# TB_sch.net
KiCad netlist of a schematic drawn in Altium Designer
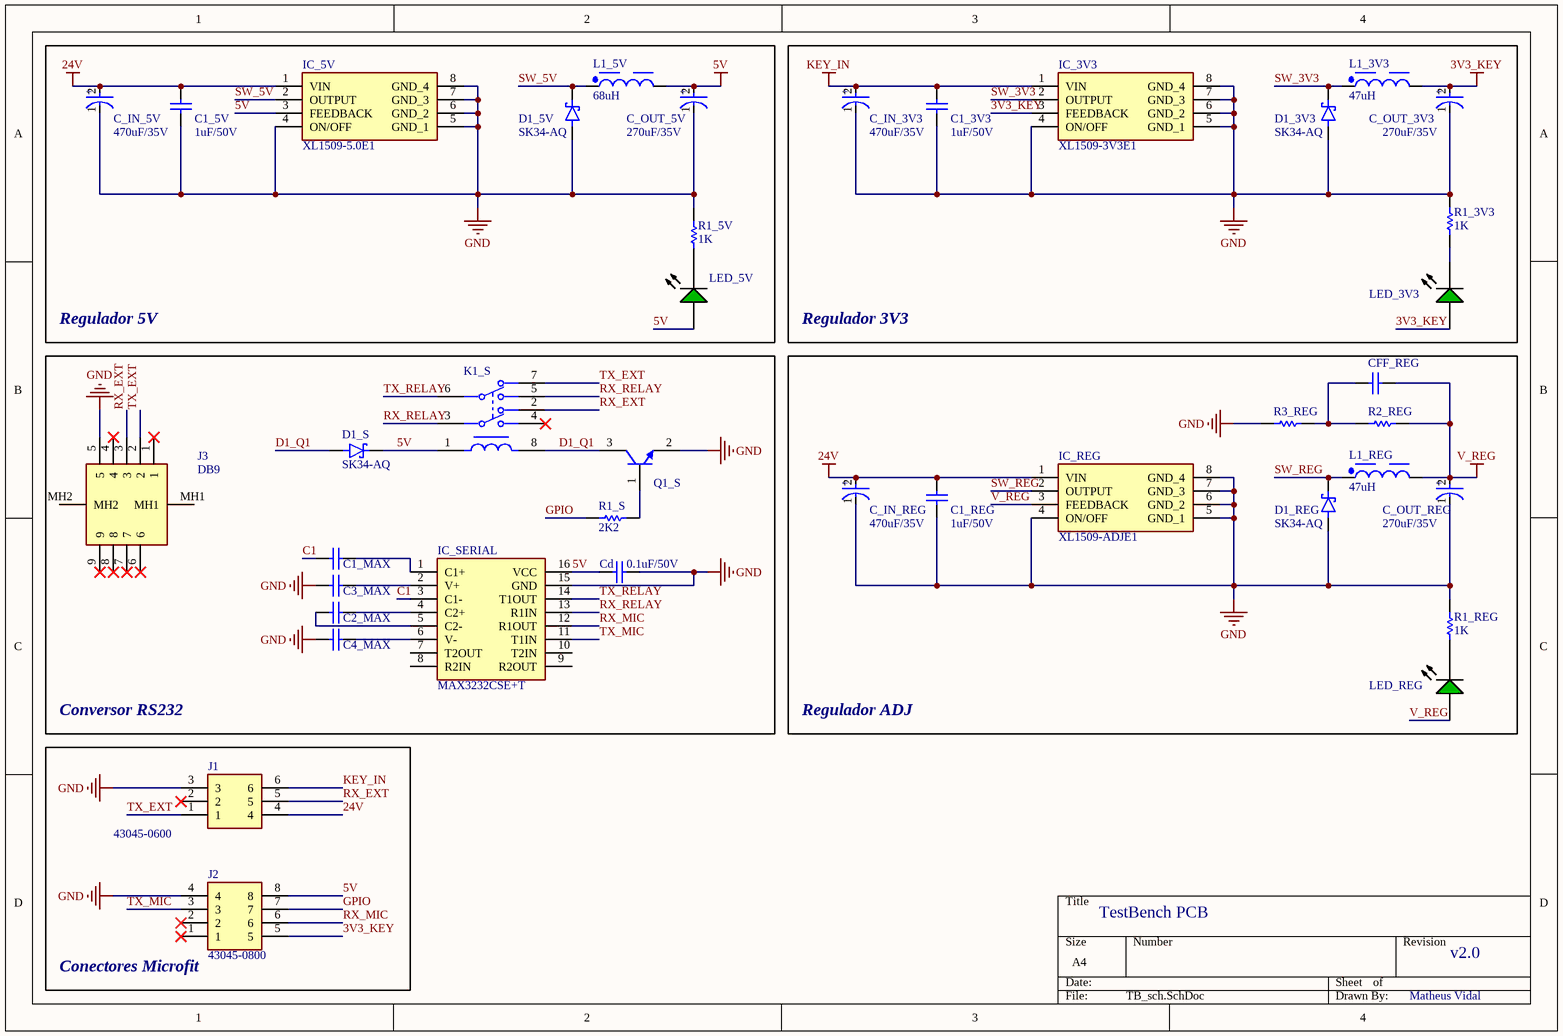
[diagram p0: TB_sch.SchDoc]

(export (version "E")
  (design (tool "Eeschema 10.0.6"))
  (components
    (comp (ref "C1_3V3")
      (value "1uF/50V")
      (footprint "CAPC2013X135X45LL10T25")
      (description "Chip Capacitor, 4.7 uF, +/- 10%, 16 V, -55 to 85 degC, 0805 (2012 Metric), RoHS, Tape and Reel")
      (fields (field (name "TOLERANCE") "10%") (field (name "PARTNUMBER") "GRM21BR61C475KA88L"))
      (libsource (lib "Altium Content Vault") (part "CAP-NP-2"))
    )
    (comp (ref "C1_5V")
      (value "1uF/50V")
      (footprint "CAPC2013X135X45LL10T25")
      (description "Chip Capacitor, 4.7 uF, +/- 10%, 16 V, -55 to 85 degC, 0805 (2012 Metric), RoHS, Tape and Reel")
      (fields (field (name "TOLERANCE") "10%") (field (name "PARTNUMBER") "GRM21BR61C475KA88L"))
      (libsource (lib "Altium Content Vault") (part "CAP-NP-2"))
    )
    (comp (ref "C1_MAX")
      (value "0.1uF/50V")
      (footprint "CAPC2013X135X45LL10T25")
      (description "Chip Capacitor, 4.7 uF, +/- 10%, 16 V, -55 to 85 degC, 0805 (2012 Metric), RoHS, Tape and Reel")
      (fields (field (name "TOLERANCE") "10%") (field (name "PARTNUMBER") "GRM21BR61C475KA88L"))
      (libsource (lib "Altium Content Vault") (part "CAP-NP-2"))
    )
    (comp (ref "C1_REG")
      (value "1uF/50V")
      (footprint "CAPC2013X135X45LL10T25")
      (description "Chip Capacitor, 4.7 uF, +/- 10%, 16 V, -55 to 85 degC, 0805 (2012 Metric), RoHS, Tape and Reel")
      (fields (field (name "TOLERANCE") "10%") (field (name "PARTNUMBER") "GRM21BR61C475KA88L"))
      (libsource (lib "Altium Content Vault") (part "CAP-NP-2"))
    )
    (comp (ref "C2_MAX")
      (value "0.1uF/50V")
      (footprint "CAPC2013X135X45LL10T25")
      (description "Chip Capacitor, 4.7 uF, +/- 10%, 16 V, -55 to 85 degC, 0805 (2012 Metric), RoHS, Tape and Reel")
      (fields (field (name "TOLERANCE") "10%") (field (name "PARTNUMBER") "GRM21BR61C475KA88L"))
      (libsource (lib "Altium Content Vault") (part "CAP-NP-2"))
    )
    (comp (ref "C3_MAX")
      (value "0.1uF/50V")
      (footprint "CAPC2013X135X45LL10T25")
      (description "Chip Capacitor, 4.7 uF, +/- 10%, 16 V, -55 to 85 degC, 0805 (2012 Metric), RoHS, Tape and Reel")
      (fields (field (name "TOLERANCE") "10%") (field (name "PARTNUMBER") "GRM21BR61C475KA88L"))
      (libsource (lib "Altium Content Vault") (part "CAP-NP-2"))
    )
    (comp (ref "C4_MAX")
      (value "0.1uF/50V")
      (footprint "CAPC2013X135X45LL10T25")
      (description "Chip Capacitor, 4.7 uF, +/- 10%, 16 V, -55 to 85 degC, 0805 (2012 Metric), RoHS, Tape and Reel")
      (fields (field (name "TOLERANCE") "10%") (field (name "PARTNUMBER") "GRM21BR61C475KA88L"))
      (libsource (lib "Altium Content Vault") (part "CAP-NP-2"))
    )
    (comp (ref "Cd")
      (value "0.1uF/50V")
      (footprint "CAPC2013X135X45LL10T25")
      (description "Chip Capacitor, 4.7 uF, +/- 10%, 16 V, -55 to 85 degC, 0805 (2012 Metric), RoHS, Tape and Reel")
      (fields (field (name "TOLERANCE") "10%") (field (name "PARTNUMBER") "GRM21BR61C475KA88L"))
      (libsource (lib "Altium Content Vault") (part "CAP-NP-2"))
    )
    (comp (ref "CFF_REG")
      (value "3.3nF/50V")
      (footprint "CAPC2013X135X45LL10T25")
      (description "Chip Capacitor, 4.7 uF, +/- 10%, 16 V, -55 to 85 degC, 0805 (2012 Metric), RoHS, Tape and Reel")
      (fields (field (name "TOLERANCE") "10%") (field (name "PARTNUMBER") "GRM21BR61C475KA88L"))
      (libsource (lib "Altium Content Vault") (part "CAP-NP-2"))
    )
    (comp (ref "C_IN_3V3")
      (value "470uF/35V")
      (footprint "FP-UCW1H221MNL1GS-MFG")
      (description "CAP ALUM 220UF 20% 50V SMD")
      (fields (field (name "TOLERANCE") "20%") (field (name "VOLTAGE") "50V"))
      (libsource (lib "Altium Content Vault") (part "cf48714ba7e38822c1575c7ec0b6d1f"))
    )
    (comp (ref "C_IN_5V")
      (value "470uF/35V")
      (footprint "FP-UCW1H221MNL1GS-MFG")
      (description "CAP ALUM 220UF 20% 50V SMD")
      (fields (field (name "TOLERANCE") "20%") (field (name "VOLTAGE") "50V"))
      (libsource (lib "Altium Content Vault") (part "cf48714ba7e38822c1575c7ec0b6d1f"))
    )
    (comp (ref "C_IN_REG")
      (value "470uF/35V")
      (footprint "FP-UCW1H221MNL1GS-MFG")
      (description "CAP ALUM 220UF 20% 50V SMD")
      (fields (field (name "TOLERANCE") "20%") (field (name "VOLTAGE") "50V"))
      (libsource (lib "Altium Content Vault") (part "cf48714ba7e38822c1575c7ec0b6d1f"))
    )
    (comp (ref "C_OUT_3V3")
      (value "270uF/35V")
      (footprint "FP-UCW1H221MNL1GS-MFG")
      (description "CAP ALUM 220UF 20% 50V SMD")
      (fields (field (name "TOLERANCE") "20%") (field (name "VOLTAGE") "50V"))
      (libsource (lib "Altium Content Vault") (part "cf48714ba7e38822c1575c7ec0b6d1f"))
    )
    (comp (ref "C_OUT_5V")
      (value "270uF/35V")
      (footprint "FP-UCW1H221MNL1GS-MFG")
      (description "CAP ALUM 220UF 20% 50V SMD")
      (fields (field (name "TOLERANCE") "20%") (field (name "VOLTAGE") "50V"))
      (libsource (lib "Altium Content Vault") (part "cf48714ba7e38822c1575c7ec0b6d1f"))
    )
    (comp (ref "C_OUT_REG")
      (value "270uF/35V")
      (footprint "FP-UCW1H221MNL1GS-MFG")
      (description "CAP ALUM 220UF 20% 50V SMD")
      (fields (field (name "TOLERANCE") "20%") (field (name "VOLTAGE") "50V"))
      (libsource (lib "Altium Content Vault") (part "cf48714ba7e38822c1575c7ec0b6d1f"))
    )
    (comp (ref "D1_3V3")
      (value "SK34-AQ")
      (footprint "DIOM7958X250N")
      (fields (field (name "MF") "Diotec Semiconductor"))
      (libsource (lib "SK34-AQ") (part "SK34-AQ"))
    )
    (comp (ref "D1_5V")
      (value "SK34-AQ")
      (footprint "DIOM7958X250N")
      (fields (field (name "MF") "Diotec Semiconductor"))
      (libsource (lib "SK34-AQ") (part "SK34-AQ"))
    )
    (comp (ref "D1_REG")
      (value "SK34-AQ")
      (footprint "DIOM7958X250N")
      (fields (field (name "MF") "Diotec Semiconductor"))
      (libsource (lib "SK34-AQ") (part "SK34-AQ"))
    )
    (comp (ref "D1_S")
      (value "SK34-AQ")
      (footprint "DIOM7958X250N")
      (fields (field (name "MF") "Diotec Semiconductor"))
      (libsource (lib "SK34-AQ") (part "SK34-AQ"))
    )
    (comp (ref "IC_3V3")
      (value "XL1509-3V3E1")
      (footprint "SamacSys:SOIC127P600X175-8N")
      (description "Integrated Circuit")
      (fields (field (name "MANUFACTURER_PART_NUMBER") "XL1509-5.0E1"))
      (libsource (lib "*") (part "XL1509-5.0E1"))
    )
    (comp (ref "IC_5V")
      (value "XL1509-5.0E1")
      (footprint "SamacSys:SOIC127P600X175-8N")
      (description "Integrated Circuit")
      (libsource (lib "*") (part "XL1509-5.0E1"))
    )
    (comp (ref "IC_REG")
      (value "XL1509-ADJE1")
      (footprint "SamacSys:SOIC127P600X175-8N")
      (description "Integrated Circuit")
      (fields (field (name "MANUFACTURER_PART_NUMBER") "XL1509-5.0E1"))
      (libsource (lib "*") (part "XL1509-5.0E1"))
    )
    (comp (ref "IC_SERIAL")
      (value "MAX3232CSE+T")
      (footprint "SamacSys:SOIC127P600X175-16N")
      (description "Integrated Circuit")
      (fields (field (name "MOUSER PART NUMBER") "700-MAX3232CSET"))
      (libsource (lib "*") (part "MAX3232CSE+T"))
    )
    (comp (ref "J1")
      (value "43045-0600")
      (footprint "SamacSys:43045-06(00,01,02,10)")
      (description "Connector")
      (fields (field (name "MOUSER PART NUMBER") "538-43045-0600"))
      (libsource (lib "*") (part "43045-0600"))
    )
    (comp (ref "J2")
      (value "43045-0800")
      (footprint "SamacSys:43045-08(00,01,02,10)")
      (description "Connector")
      (fields (field (name "MOUSER PART NUMBER") "538-43045-0800"))
      (libsource (lib "*") (part "43045-0800"))
    )
    (comp (ref "J3")
      (value "DB9")
      (footprint "SamacSys:L77DFE09S1AMN")
      (description "Connector")
      (fields
        (field (name "MANUFACTURER_PART_NUMBER") "L77DFE09S1AMN")
        (field (name "MOUSER PART NUMBER") "523-L77DFE09S1AMN")
      )
      (libsource (lib "*") (part "L77DFE09S1AMN"))
    )
    (comp (ref "K1_S")
      (value "G6K-2F-Y-TR-DC5")
      (footprint "FP-G6K-2F-Y-TR-DC5-MFG")
      (description "RELAY TELECOM DPDT 1A 5VDC")
      (fields
        (field (name "OCTOPART") "https://octopart.com/g6k-2f-y-tr-dc5-omron-697853")
        (field (name "MANUFACTURER") "Omron")
      )
      (libsource (lib "Altium Content Vault") (part "58c38101009d5ebbf9054263c5b66d6"))
    )
    (comp (ref "L1_3V3")
      (value "47uH")
      (footprint "WE-PD_1280")
      (fields (field (name "TOLERANCE") "20%"))
      (libsource (lib "Altium Content Vault") (part "Inductor - 2"))
    )
    (comp (ref "L1_5V")
      (value "68uH")
      (footprint "WE-PD_1280")
      (fields (field (name "TOLERANCE") "20%"))
      (libsource (lib "Altium Content Vault") (part "Inductor - 2"))
    )
    (comp (ref "L1_REG")
      (value "47uH")
      (footprint "WE-PD_1280")
      (fields (field (name "TOLERANCE") "20%"))
      (libsource (lib "Altium Content Vault") (part "Inductor - 2"))
    )
    (comp (ref "LED_3V3")
      (value "~")
      (footprint "AVAG-HSMX-C170_V")
      (description "Chip LED, Green, 2.2 V, -40 to 85 degC, 2-Pin SMD, Pb-Free, Tape and Reel")
      (fields (field (name "MANUFACTURER") "Avago"))
      (libsource (lib "Altium Content Vault") (part "LED_GREEN_A1K2-2"))
    )
    (comp (ref "LED_5V")
      (value "~")
      (footprint "AVAG-HSMX-C170_V")
      (description "Chip LED, Green, 2.2 V, -40 to 85 degC, 2-Pin SMD, Pb-Free, Tape and Reel")
      (fields (field (name "MANUFACTURER") "Avago"))
      (libsource (lib "Altium Content Vault") (part "LED_GREEN_A1K2-2"))
    )
    (comp (ref "LED_REG")
      (value "~")
      (footprint "AVAG-HSMX-C170_V")
      (description "Chip LED, Green, 2.2 V, -40 to 85 degC, 2-Pin SMD, Pb-Free, Tape and Reel")
      (fields (field (name "MANUFACTURER") "Avago"))
      (libsource (lib "Altium Content Vault") (part "LED_GREEN_A1K2-2"))
    )
    (comp (ref "Q1_S")
      (value "MMBT2222LT1G")
      (footprint "ONSC-SOT-23-3-318-08_V")
      (description "General Purpose Transistor, NPN Silicon, 3-Pin SOT-23, Pb-Free, Tape and Reel")
      (fields (field (name "MANUFACTURER") "On Semiconductor"))
      (libsource (lib "Altium Content Vault") (part "ONSC-NPN-B1E2C3-3"))
    )
    (comp (ref "R1_3V3")
      (value "1K")
      (footprint "RESC2013X50X30LL20T20")
      (fields (field (name "MANUFACTURER") "Vishay Dale") (field (name "PART NUMBER") "CRCW08050000Z0EA"))
      (libsource (lib "Altium Content Vault") (part "RES"))
    )
    (comp (ref "R1_5V")
      (value "1K")
      (footprint "RESC2013X50X30LL20T20")
      (fields (field (name "MANUFACTURER") "Vishay Dale") (field (name "PART NUMBER") "CRCW08050000Z0EA"))
      (libsource (lib "Altium Content Vault") (part "RES"))
    )
    (comp (ref "R1_REG")
      (value "1K")
      (footprint "RESC2013X50X30LL20T20")
      (fields (field (name "MANUFACTURER") "Vishay Dale") (field (name "PART NUMBER") "CRCW08050000Z0EA"))
      (libsource (lib "Altium Content Vault") (part "RES"))
    )
    (comp (ref "R1_S")
      (value "2K2")
      (footprint "RESC2013X50X30LL20T20")
      (fields (field (name "MANUFACTURER") "Vishay Dale") (field (name "PART NUMBER") "CRCW08050000Z0EA"))
      (libsource (lib "Altium Content Vault") (part "RES"))
    )
    (comp (ref "R2_REG")
      (value "CRCW08050000Z0EA")
      (footprint "RESC2013X50X30LL20T20")
      (fields (field (name "MANUFACTURER") "Vishay Dale"))
      (libsource (lib "Altium Content Vault") (part "RES"))
    )
    (comp (ref "R3_REG")
      (value "CRCW08050000Z0EA")
      (footprint "RESC2013X50X30LL20T20")
      (fields (field (name "MANUFACTURER") "Vishay Dale"))
      (libsource (lib "Altium Content Vault") (part "RES"))
    )
  )
  (nets
    (net (code "1") (name "/C1") (class "Default")
      (node (ref "C1_MAX") (pin "2") (pinfunction "2_2") (pintype "passive"))
      (node (ref "IC_SERIAL") (pin "3") (pinfunction "C1-_3") (pintype "passive"))
    )
    (net (code "2") (name "/D1_Q1") (class "Default")
      (node (ref "D1_S") (pin "A") (pinfunction "A_A") (pintype "passive"))
      (node (ref "K1_S") (pin "8") (pinfunction "8_8") (pintype "passive"))
      (node (ref "Q1_S") (pin "3") (pinfunction "C_3") (pintype "passive"))
    )
    (net (code "3") (name "/GPIO") (class "Default")
      (node (ref "J2") (pin "7") (pinfunction "7_7") (pintype "passive"))
      (node (ref "R1_S") (pin "2") (pinfunction "2_2") (pintype "passive"))
    )
    (net (code "4") (name "/RX_EXT") (class "Default")
      (node (ref "J1") (pin "5") (pinfunction "5_5") (pintype "passive"))
      (node (ref "J3") (pin "3") (pinfunction "3_3") (pintype "passive"))
      (node (ref "K1_S") (pin "2") (pinfunction "2_2") (pintype "passive"))
    )
    (net (code "5") (name "/RX_MIC") (class "Default")
      (node (ref "IC_SERIAL") (pin "12") (pinfunction "R1OUT_12") (pintype "passive"))
      (node (ref "J2") (pin "6") (pinfunction "6_6") (pintype "passive"))
    )
    (net (code "6") (name "/RX_RELAY") (class "Default")
      (node (ref "IC_SERIAL") (pin "13") (pinfunction "R1IN_13") (pintype "passive"))
      (node (ref "K1_S") (pin "3") (pinfunction "3_3") (pintype "passive"))
      (node (ref "K1_S") (pin "5") (pinfunction "5_5") (pintype "passive"))
    )
    (net (code "7") (name "/SW_3V3") (class "Default")
      (node (ref "D1_3V3") (pin "C") (pinfunction "K_C") (pintype "passive"))
      (node (ref "IC_3V3") (pin "2") (pinfunction "OUTPUT_2") (pintype "passive"))
      (node (ref "L1_3V3") (pin "1") (pinfunction "1_1") (pintype "passive"))
    )
    (net (code "8") (name "/SW_5V") (class "Default")
      (node (ref "D1_5V") (pin "C") (pinfunction "K_C") (pintype "passive"))
      (node (ref "IC_5V") (pin "2") (pinfunction "OUTPUT_2") (pintype "passive"))
      (node (ref "L1_5V") (pin "1") (pinfunction "1_1") (pintype "passive"))
    )
    (net (code "9") (name "/SW_REG") (class "Default")
      (node (ref "D1_REG") (pin "C") (pinfunction "K_C") (pintype "passive"))
      (node (ref "IC_REG") (pin "2") (pinfunction "OUTPUT_2") (pintype "passive"))
      (node (ref "L1_REG") (pin "1") (pinfunction "1_1") (pintype "passive"))
    )
    (net (code "10") (name "/TX_EXT") (class "Default")
      (node (ref "J1") (pin "1") (pinfunction "1_1") (pintype "passive"))
      (node (ref "J3") (pin "2") (pinfunction "2_2") (pintype "passive"))
      (node (ref "K1_S") (pin "7") (pinfunction "7_7") (pintype "passive"))
    )
    (net (code "11") (name "/TX_MIC") (class "Default")
      (node (ref "IC_SERIAL") (pin "11") (pinfunction "T1IN_11") (pintype "passive"))
      (node (ref "J2") (pin "3") (pinfunction "3_3") (pintype "passive"))
    )
    (net (code "12") (name "/TX_RELAY") (class "Default")
      (node (ref "IC_SERIAL") (pin "14") (pinfunction "T1OUT_14") (pintype "passive"))
      (node (ref "K1_S") (pin "6") (pinfunction "6_6") (pintype "passive"))
    )
    (net (code "13") (name "3V3_KEY") (class "Default")
      (node (ref "C_OUT_3V3") (pin "2") (pinfunction "A_2") (pintype "passive"))
      (node (ref "IC_3V3") (pin "3") (pinfunction "FEEDBACK_3") (pintype "passive"))
      (node (ref "J2") (pin "5") (pinfunction "5_5") (pintype "passive"))
      (node (ref "L1_3V3") (pin "2") (pinfunction "2_2") (pintype "passive"))
      (node (ref "LED_3V3") (pin "1") (pinfunction "A_1") (pintype "passive"))
    )
    (net (code "14") (name "5V") (class "Default")
      (node (ref "C_OUT_5V") (pin "2") (pinfunction "A_2") (pintype "passive"))
      (node (ref "Cd") (pin "2") (pinfunction "2_2") (pintype "passive"))
      (node (ref "D1_S") (pin "C") (pinfunction "K_C") (pintype "passive"))
      (node (ref "IC_5V") (pin "3") (pinfunction "FEEDBACK_3") (pintype "passive"))
      (node (ref "IC_SERIAL") (pin "16") (pinfunction "VCC_16") (pintype "passive"))
      (node (ref "J2") (pin "8") (pinfunction "8_8") (pintype "passive"))
      (node (ref "K1_S") (pin "1") (pinfunction "1_1") (pintype "passive"))
      (node (ref "L1_5V") (pin "2") (pinfunction "2_2") (pintype "passive"))
      (node (ref "LED_5V") (pin "1") (pinfunction "A_1") (pintype "passive"))
    )
    (net (code "15") (name "24V") (class "Default")
      (node (ref "C1_5V") (pin "2") (pinfunction "2_2") (pintype "passive"))
      (node (ref "C1_REG") (pin "2") (pinfunction "2_2") (pintype "passive"))
      (node (ref "C_IN_5V") (pin "2") (pinfunction "A_2") (pintype "passive"))
      (node (ref "C_IN_REG") (pin "2") (pinfunction "A_2") (pintype "passive"))
      (node (ref "IC_5V") (pin "1") (pinfunction "VIN_1") (pintype "passive"))
      (node (ref "IC_REG") (pin "1") (pinfunction "VIN_1") (pintype "passive"))
      (node (ref "J1") (pin "4") (pinfunction "4_4") (pintype "passive"))
    )
    (net (code "16") (name "GND") (class "Default")
      (node (ref "C1_3V3") (pin "1") (pinfunction "1_1") (pintype "passive"))
      (node (ref "C1_5V") (pin "1") (pinfunction "1_1") (pintype "passive"))
      (node (ref "C1_REG") (pin "1") (pinfunction "1_1") (pintype "passive"))
      (node (ref "C3_MAX") (pin "2") (pinfunction "2_2") (pintype "passive"))
      (node (ref "C4_MAX") (pin "2") (pinfunction "2_2") (pintype "passive"))
      (node (ref "C_IN_3V3") (pin "1") (pinfunction "C_1") (pintype "passive"))
      (node (ref "C_IN_5V") (pin "1") (pinfunction "C_1") (pintype "passive"))
      (node (ref "C_IN_REG") (pin "1") (pinfunction "C_1") (pintype "passive"))
      (node (ref "C_OUT_3V3") (pin "1") (pinfunction "C_1") (pintype "passive"))
      (node (ref "C_OUT_5V") (pin "1") (pinfunction "C_1") (pintype "passive"))
      (node (ref "C_OUT_REG") (pin "1") (pinfunction "C_1") (pintype "passive"))
      (node (ref "Cd") (pin "1") (pinfunction "1_1") (pintype "passive"))
      (node (ref "D1_3V3") (pin "A") (pinfunction "A_A") (pintype "passive"))
      (node (ref "D1_5V") (pin "A") (pinfunction "A_A") (pintype "passive"))
      (node (ref "D1_REG") (pin "A") (pinfunction "A_A") (pintype "passive"))
      (node (ref "IC_3V3") (pin "4") (pinfunction "ON/OFF_4") (pintype "passive"))
      (node (ref "IC_3V3") (pin "5") (pinfunction "GND_1_5") (pintype "passive"))
      (node (ref "IC_3V3") (pin "6") (pinfunction "GND_2_6") (pintype "passive"))
      (node (ref "IC_3V3") (pin "7") (pinfunction "GND_3_7") (pintype "passive"))
      (node (ref "IC_3V3") (pin "8") (pinfunction "GND_4_8") (pintype "passive"))
      (node (ref "IC_5V") (pin "4") (pinfunction "ON/OFF_4") (pintype "passive"))
      (node (ref "IC_5V") (pin "5") (pinfunction "GND_1_5") (pintype "passive"))
      (node (ref "IC_5V") (pin "6") (pinfunction "GND_2_6") (pintype "passive"))
      (node (ref "IC_5V") (pin "7") (pinfunction "GND_3_7") (pintype "passive"))
      (node (ref "IC_5V") (pin "8") (pinfunction "GND_4_8") (pintype "passive"))
      (node (ref "IC_REG") (pin "4") (pinfunction "ON/OFF_4") (pintype "passive"))
      (node (ref "IC_REG") (pin "5") (pinfunction "GND_1_5") (pintype "passive"))
      (node (ref "IC_REG") (pin "6") (pinfunction "GND_2_6") (pintype "passive"))
      (node (ref "IC_REG") (pin "7") (pinfunction "GND_3_7") (pintype "passive"))
      (node (ref "IC_REG") (pin "8") (pinfunction "GND_4_8") (pintype "passive"))
      (node (ref "IC_SERIAL") (pin "15") (pinfunction "GND_15") (pintype "passive"))
      (node (ref "J1") (pin "3") (pinfunction "3_3") (pintype "passive"))
      (node (ref "J2") (pin "4") (pinfunction "4_4") (pintype "passive"))
      (node (ref "J3") (pin "5") (pinfunction "5_5") (pintype "passive"))
      (node (ref "Q1_S") (pin "2") (pinfunction "E_2") (pintype "passive"))
      (node (ref "R1_3V3") (pin "2") (pinfunction "2_2") (pintype "passive"))
      (node (ref "R1_5V") (pin "2") (pinfunction "2_2") (pintype "passive"))
      (node (ref "R1_REG") (pin "2") (pinfunction "2_2") (pintype "passive"))
      (node (ref "R3_REG") (pin "1") (pinfunction "1_1") (pintype "passive"))
    )
    (net (code "17") (name "KEY_IN") (class "Default")
      (node (ref "C1_3V3") (pin "2") (pinfunction "2_2") (pintype "passive"))
      (node (ref "C_IN_3V3") (pin "2") (pinfunction "A_2") (pintype "passive"))
      (node (ref "IC_3V3") (pin "1") (pinfunction "VIN_1") (pintype "passive"))
      (node (ref "J1") (pin "6") (pinfunction "6_6") (pintype "passive"))
    )
    (net (code "18") (name "Net-(CFF_REG-Pad2)") (class "Default")
      (node (ref "CFF_REG") (pin "2") (pinfunction "2_2") (pintype "passive"))
      (node (ref "R2_REG") (pin "1") (pinfunction "1_1") (pintype "passive"))
      (node (ref "R3_REG") (pin "2") (pinfunction "2_2") (pintype "passive"))
    )
    (net (code "19") (name "Net-(IC_SERIAL-C1+)") (class "Default")
      (node (ref "C1_MAX") (pin "1") (pinfunction "1_1") (pintype "passive"))
      (node (ref "IC_SERIAL") (pin "1") (pinfunction "C1+_1") (pintype "passive"))
    )
    (net (code "20") (name "Net-(IC_SERIAL-C2+)") (class "Default")
      (node (ref "C2_MAX") (pin "1") (pinfunction "1_1") (pintype "passive"))
      (node (ref "IC_SERIAL") (pin "4") (pinfunction "C2+_4") (pintype "passive"))
    )
    (net (code "21") (name "Net-(IC_SERIAL-C2-)") (class "Default")
      (node (ref "C2_MAX") (pin "2") (pinfunction "2_2") (pintype "passive"))
      (node (ref "IC_SERIAL") (pin "5") (pinfunction "C2-_5") (pintype "passive"))
    )
    (net (code "22") (name "Net-(IC_SERIAL-V+)") (class "Default")
      (node (ref "C3_MAX") (pin "1") (pinfunction "1_1") (pintype "passive"))
      (node (ref "IC_SERIAL") (pin "2") (pinfunction "V+_2") (pintype "passive"))
    )
    (net (code "23") (name "Net-(IC_SERIAL-V-)") (class "Default")
      (node (ref "C4_MAX") (pin "1") (pinfunction "1_1") (pintype "passive"))
      (node (ref "IC_SERIAL") (pin "6") (pinfunction "V-_6") (pintype "passive"))
    )
    (net (code "24") (name "Net-(LED_3V3-K)") (class "Default")
      (node (ref "LED_3V3") (pin "2") (pinfunction "K_2") (pintype "passive"))
      (node (ref "R1_3V3") (pin "1") (pinfunction "1_1") (pintype "passive"))
    )
    (net (code "25") (name "Net-(LED_5V-K)") (class "Default")
      (node (ref "LED_5V") (pin "2") (pinfunction "K_2") (pintype "passive"))
      (node (ref "R1_5V") (pin "1") (pinfunction "1_1") (pintype "passive"))
    )
    (net (code "26") (name "Net-(LED_REG-K)") (class "Default")
      (node (ref "LED_REG") (pin "2") (pinfunction "K_2") (pintype "passive"))
      (node (ref "R1_REG") (pin "1") (pinfunction "1_1") (pintype "passive"))
    )
    (net (code "27") (name "Net-(Q1_S-B)") (class "Default")
      (node (ref "Q1_S") (pin "1") (pinfunction "B_1") (pintype "passive"))
      (node (ref "R1_S") (pin "1") (pinfunction "1_1") (pintype "passive"))
    )
    (net (code "28") (name "V_REG") (class "Default")
      (node (ref "CFF_REG") (pin "1") (pinfunction "1_1") (pintype "passive"))
      (node (ref "C_OUT_REG") (pin "2") (pinfunction "A_2") (pintype "passive"))
      (node (ref "IC_REG") (pin "3") (pinfunction "FEEDBACK_3") (pintype "passive"))
      (node (ref "L1_REG") (pin "2") (pinfunction "2_2") (pintype "passive"))
      (node (ref "LED_REG") (pin "1") (pinfunction "A_1") (pintype "passive"))
      (node (ref "R2_REG") (pin "2") (pinfunction "2_2") (pintype "passive"))
    )
    (net (code "29") (name "unconnected-(IC_SERIAL-R2IN-Pad8)") (class "Default")
      (node (ref "IC_SERIAL") (pin "8") (pinfunction "R2IN_8") (pintype "passive"))
    )
    (net (code "30") (name "unconnected-(IC_SERIAL-R2OUT-Pad9)") (class "Default")
      (node (ref "IC_SERIAL") (pin "9") (pinfunction "R2OUT_9") (pintype "passive"))
    )
    (net (code "31") (name "unconnected-(IC_SERIAL-T2IN-Pad10)") (class "Default")
      (node (ref "IC_SERIAL") (pin "10") (pinfunction "T2IN_10") (pintype "passive"))
    )
    (net (code "32") (name "unconnected-(IC_SERIAL-T2OUT-Pad7)") (class "Default")
      (node (ref "IC_SERIAL") (pin "7") (pinfunction "T2OUT_7") (pintype "passive"))
    )
    (net (code "33") (name "unconnected-(J1-Pad2)") (class "Default")
      (node (ref "J1") (pin "2") (pinfunction "2_2") (pintype "passive+no_connect"))
    )
    (net (code "34") (name "unconnected-(J2-Pad1)") (class "Default")
      (node (ref "J2") (pin "1") (pinfunction "1_1") (pintype "passive+no_connect"))
    )
    (net (code "35") (name "unconnected-(J2-Pad2)") (class "Default")
      (node (ref "J2") (pin "2") (pinfunction "2_2") (pintype "passive+no_connect"))
    )
    (net (code "36") (name "unconnected-(J3-Pad1)") (class "Default")
      (node (ref "J3") (pin "1") (pinfunction "1_1") (pintype "passive+no_connect"))
    )
    (net (code "37") (name "unconnected-(J3-Pad4)") (class "Default")
      (node (ref "J3") (pin "4") (pinfunction "4_4") (pintype "passive+no_connect"))
    )
    (net (code "38") (name "unconnected-(J3-Pad6)") (class "Default")
      (node (ref "J3") (pin "6") (pinfunction "6_6") (pintype "passive+no_connect"))
    )
    (net (code "39") (name "unconnected-(J3-Pad7)") (class "Default")
      (node (ref "J3") (pin "7") (pinfunction "7_7") (pintype "passive+no_connect"))
    )
    (net (code "40") (name "unconnected-(J3-Pad8)") (class "Default")
      (node (ref "J3") (pin "8") (pinfunction "8_8") (pintype "passive+no_connect"))
    )
    (net (code "41") (name "unconnected-(J3-Pad9)") (class "Default")
      (node (ref "J3") (pin "9") (pinfunction "9_9") (pintype "passive+no_connect"))
    )
    (net (code "42") (name "unconnected-(J3-PadMH1)") (class "Default")
      (node (ref "J3") (pin "MH1") (pinfunction "MH1_MH1") (pintype "passive"))
    )
    (net (code "43") (name "unconnected-(J3-PadMH2)") (class "Default")
      (node (ref "J3") (pin "MH2") (pinfunction "MH2_MH2") (pintype "passive"))
    )
    (net (code "44") (name "unconnected-(K1_S-Pad4)") (class "Default")
      (node (ref "K1_S") (pin "4") (pinfunction "4_4") (pintype "passive+no_connect"))
    )
  )
)
